# arduinoboardwithphotoresistors3.net
KiCad netlist of a schematic drawn in EAGLE
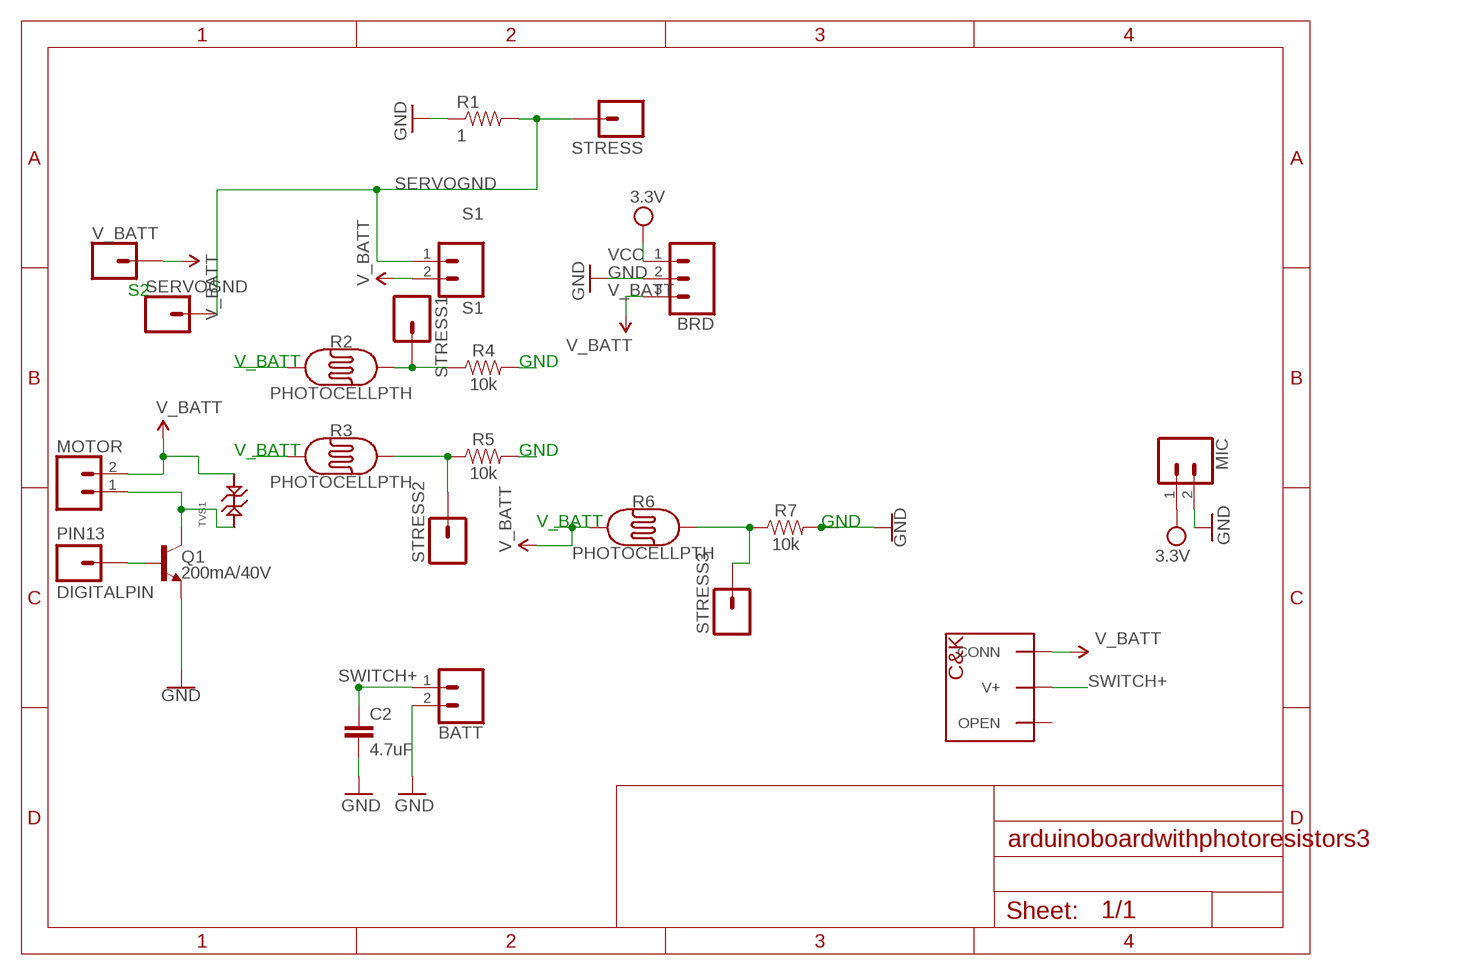
[diagram p0: schematic, sheet 1]

(export (version "E")
  (design (tool "Eeschema 10.0.6"))
  (components
    (comp (ref "BATT")
      (value "CONN_02")
      (footprint "eagle-import:1X02")
      (libsource (lib "eagle-import") (part "CONN_02"))
    )
    (comp (ref "BRD")
      (value "CONN_03")
      (footprint "eagle-import:1X03")
      (libsource (lib "eagle-import") (part "CONN_03"))
    )
    (comp (ref "C2")
      (value "4.7uF")
      (footprint "eagle-import:0603-CAP")
      (libsource (lib "eagle-import") (part "4.7UF-6.3V-10%(0603)0603"))
    )
    (comp (ref "MIC")
      (value "CONN_02")
      (footprint "eagle-import:1X02")
      (libsource (lib "eagle-import") (part "CONN_02"))
    )
    (comp (ref "MOTOR")
      (value "CONN_02")
      (footprint "eagle-import:1X02")
      (libsource (lib "eagle-import") (part "CONN_02"))
    )
    (comp (ref "PIN13")
      (value "DIGITALPIN")
      (footprint "eagle-import:1X01")
      (libsource (lib "eagle-import") (part "M01PTH"))
    )
    (comp (ref "Q1")
      (value "200mA/40V")
      (footprint "eagle-import:TO-92")
      (libsource (lib "eagle-import") (part "TRANS_NPN-2N3904"))
    )
    (comp (ref "R1")
      (value "1")
      (footprint "eagle-import:0603-RES")
      (libsource (lib "eagle-import") (part "2.0KOHM1/10W5%(0603)"))
    )
    (comp (ref "R2")
      (value "PHOTOCELLPTH")
      (footprint "eagle-import:PHOTOCELL")
      (libsource (lib "eagle-import") (part "PHOTOCELLPTH"))
    )
    (comp (ref "R3")
      (value "PHOTOCELLPTH")
      (footprint "eagle-import:PHOTOCELL")
      (libsource (lib "eagle-import") (part "PHOTOCELLPTH"))
    )
    (comp (ref "R4")
      (value "10k")
      (footprint "eagle-import:0603")
      (libsource (lib "eagle-import") (part "10KOHM-0603-1/10W-1%"))
    )
    (comp (ref "R5")
      (value "10k")
      (footprint "eagle-import:0603")
      (libsource (lib "eagle-import") (part "10KOHM-0603-1/10W-1%"))
    )
    (comp (ref "R6")
      (value "PHOTOCELLPTH")
      (footprint "eagle-import:PHOTOCELL")
      (libsource (lib "eagle-import") (part "PHOTOCELLPTH"))
    )
    (comp (ref "R7")
      (value "10k")
      (footprint "eagle-import:0603")
      (libsource (lib "eagle-import") (part "10KOHM-0603-1/10W-1%"))
    )
    (comp (ref "S1")
      (value "S1")
      (footprint "eagle-import:1X02")
      (libsource (lib "eagle-import") (part "CONN_02"))
    )
    (comp (ref "SERVOGND")
      (value "CONN_01")
      (footprint "eagle-import:1X01")
      (libsource (lib "eagle-import") (part "CONN_01"))
    )
    (comp (ref "STRESS")
      (value "M01PTH")
      (footprint "eagle-import:1X01")
      (libsource (lib "eagle-import") (part "M01PTH"))
    )
    (comp (ref "STRESS1")
      (value "M01PTH")
      (footprint "eagle-import:1X01")
      (libsource (lib "eagle-import") (part "M01PTH"))
    )
    (comp (ref "STRESS2")
      (value "M01PTH")
      (footprint "eagle-import:1X01")
      (libsource (lib "eagle-import") (part "M01PTH"))
    )
    (comp (ref "STRESS3")
      (value "M01PTH")
      (footprint "eagle-import:1X01")
      (libsource (lib "eagle-import") (part "M01PTH"))
    )
    (comp (ref "TVS1")
      (value "TVS_DIODE_SOD-923")
      (footprint "eagle-import:SOD-923")
      (libsource (lib "eagle-import") (part "TVS_DIODE_SOD-923"))
    )
    (comp (ref "U$1")
      (value "WILL-BLACKSLIDESWITCH")
      (footprint "eagle-import:WILL-BLACKSLIDESWITCH")
      (libsource (lib "eagle-import") (part "WILL-BLACKSLIDESWITCH"))
    )
    (comp (ref "V_BATT")
      (value "CONN_01")
      (footprint "eagle-import:1X01")
      (libsource (lib "eagle-import") (part "CONN_01"))
    )
  )
  (nets
    (net (code "1") (name "/SERVOGND") (class "Default")
      (node (ref "R1") (pin "2") (pinfunction "2_2") (pintype "passive"))
      (node (ref "S1") (pin "1") (pinfunction "1_1") (pintype "passive"))
      (node (ref "SERVOGND") (pin "1") (pinfunction "1_1") (pintype "passive"))
      (node (ref "STRESS") (pin "1") (pinfunction "1_1") (pintype "passive"))
    )
    (net (code "2") (name "/SWITCH+") (class "Default")
      (node (ref "BATT") (pin "1") (pinfunction "1_1") (pintype "passive"))
      (node (ref "C2") (pin "1") (pinfunction "1_1") (pintype "passive"))
      (node (ref "U$1") (pin "V+") (pinfunction "V+_V+") (pintype "bidirectional"))
    )
    (net (code "3") (name "3.3V") (class "Default")
      (node (ref "BRD") (pin "1") (pinfunction "1_1") (pintype "passive"))
      (node (ref "MIC") (pin "1") (pinfunction "1_1") (pintype "passive"))
    )
    (net (code "4") (name "GND") (class "Default")
      (node (ref "BATT") (pin "2") (pinfunction "2_2") (pintype "passive"))
      (node (ref "BRD") (pin "2") (pinfunction "2_2") (pintype "passive"))
      (node (ref "C2") (pin "2") (pinfunction "2_2") (pintype "passive"))
      (node (ref "MIC") (pin "2") (pinfunction "2_2") (pintype "passive"))
      (node (ref "Q1") (pin "1") (pinfunction "E_1") (pintype "passive"))
      (node (ref "R1") (pin "1") (pinfunction "1_1") (pintype "passive"))
      (node (ref "R4") (pin "2") (pinfunction "2_2") (pintype "passive"))
      (node (ref "R5") (pin "2") (pinfunction "2_2") (pintype "passive"))
      (node (ref "R7") (pin "2") (pinfunction "2_2") (pintype "passive"))
    )
    (net (code "5") (name "Net-(Q1-B)") (class "Default")
      (node (ref "PIN13") (pin "1") (pinfunction "1_1") (pintype "passive"))
      (node (ref "Q1") (pin "2") (pinfunction "B_2") (pintype "passive"))
    )
    (net (code "6") (name "Net-(Q1-C)") (class "Default")
      (node (ref "MOTOR") (pin "1") (pinfunction "1_1") (pintype "passive"))
      (node (ref "Q1") (pin "3") (pinfunction "C_3") (pintype "passive"))
      (node (ref "TVS1") (pin "P$1") (pinfunction "P$1_P$1") (pintype "bidirectional"))
    )
    (net (code "7") (name "Net-(R2-P$2)") (class "Default")
      (node (ref "R2") (pin "2") (pinfunction "P$2_2") (pintype "bidirectional"))
      (node (ref "R4") (pin "1") (pinfunction "1_1") (pintype "passive"))
      (node (ref "STRESS1") (pin "1") (pinfunction "1_1") (pintype "passive"))
    )
    (net (code "8") (name "Net-(R3-P$2)") (class "Default")
      (node (ref "R3") (pin "2") (pinfunction "P$2_2") (pintype "bidirectional"))
      (node (ref "R5") (pin "1") (pinfunction "1_1") (pintype "passive"))
      (node (ref "STRESS2") (pin "1") (pinfunction "1_1") (pintype "passive"))
    )
    (net (code "9") (name "Net-(R6-P$2)") (class "Default")
      (node (ref "R6") (pin "2") (pinfunction "P$2_2") (pintype "bidirectional"))
      (node (ref "R7") (pin "1") (pinfunction "1_1") (pintype "passive"))
      (node (ref "STRESS3") (pin "1") (pinfunction "1_1") (pintype "passive"))
    )
    (net (code "10") (name "V_BATT") (class "Default")
      (node (ref "BRD") (pin "3") (pinfunction "3_3") (pintype "passive"))
      (node (ref "MOTOR") (pin "2") (pinfunction "2_2") (pintype "passive"))
      (node (ref "R2") (pin "1") (pinfunction "P$1_1") (pintype "bidirectional"))
      (node (ref "R3") (pin "1") (pinfunction "P$1_1") (pintype "bidirectional"))
      (node (ref "R6") (pin "1") (pinfunction "P$1_1") (pintype "bidirectional"))
      (node (ref "S1") (pin "2") (pinfunction "2_2") (pintype "passive"))
      (node (ref "TVS1") (pin "P$2") (pinfunction "P$2_P$2") (pintype "bidirectional"))
      (node (ref "U$1") (pin "CONN") (pinfunction "CONN_CONN") (pintype "bidirectional"))
      (node (ref "V_BATT") (pin "1") (pinfunction "1_1") (pintype "passive"))
    )
    (net (code "11") (name "unconnected-(U$1-OPEN-PadNC)") (class "Default")
      (node (ref "U$1") (pin "NC") (pinfunction "OPEN_NC") (pintype "bidirectional"))
    )
  )
)
